# ATRescueBoard.net
KiCad netlist of a schematic drawn in EAGLE
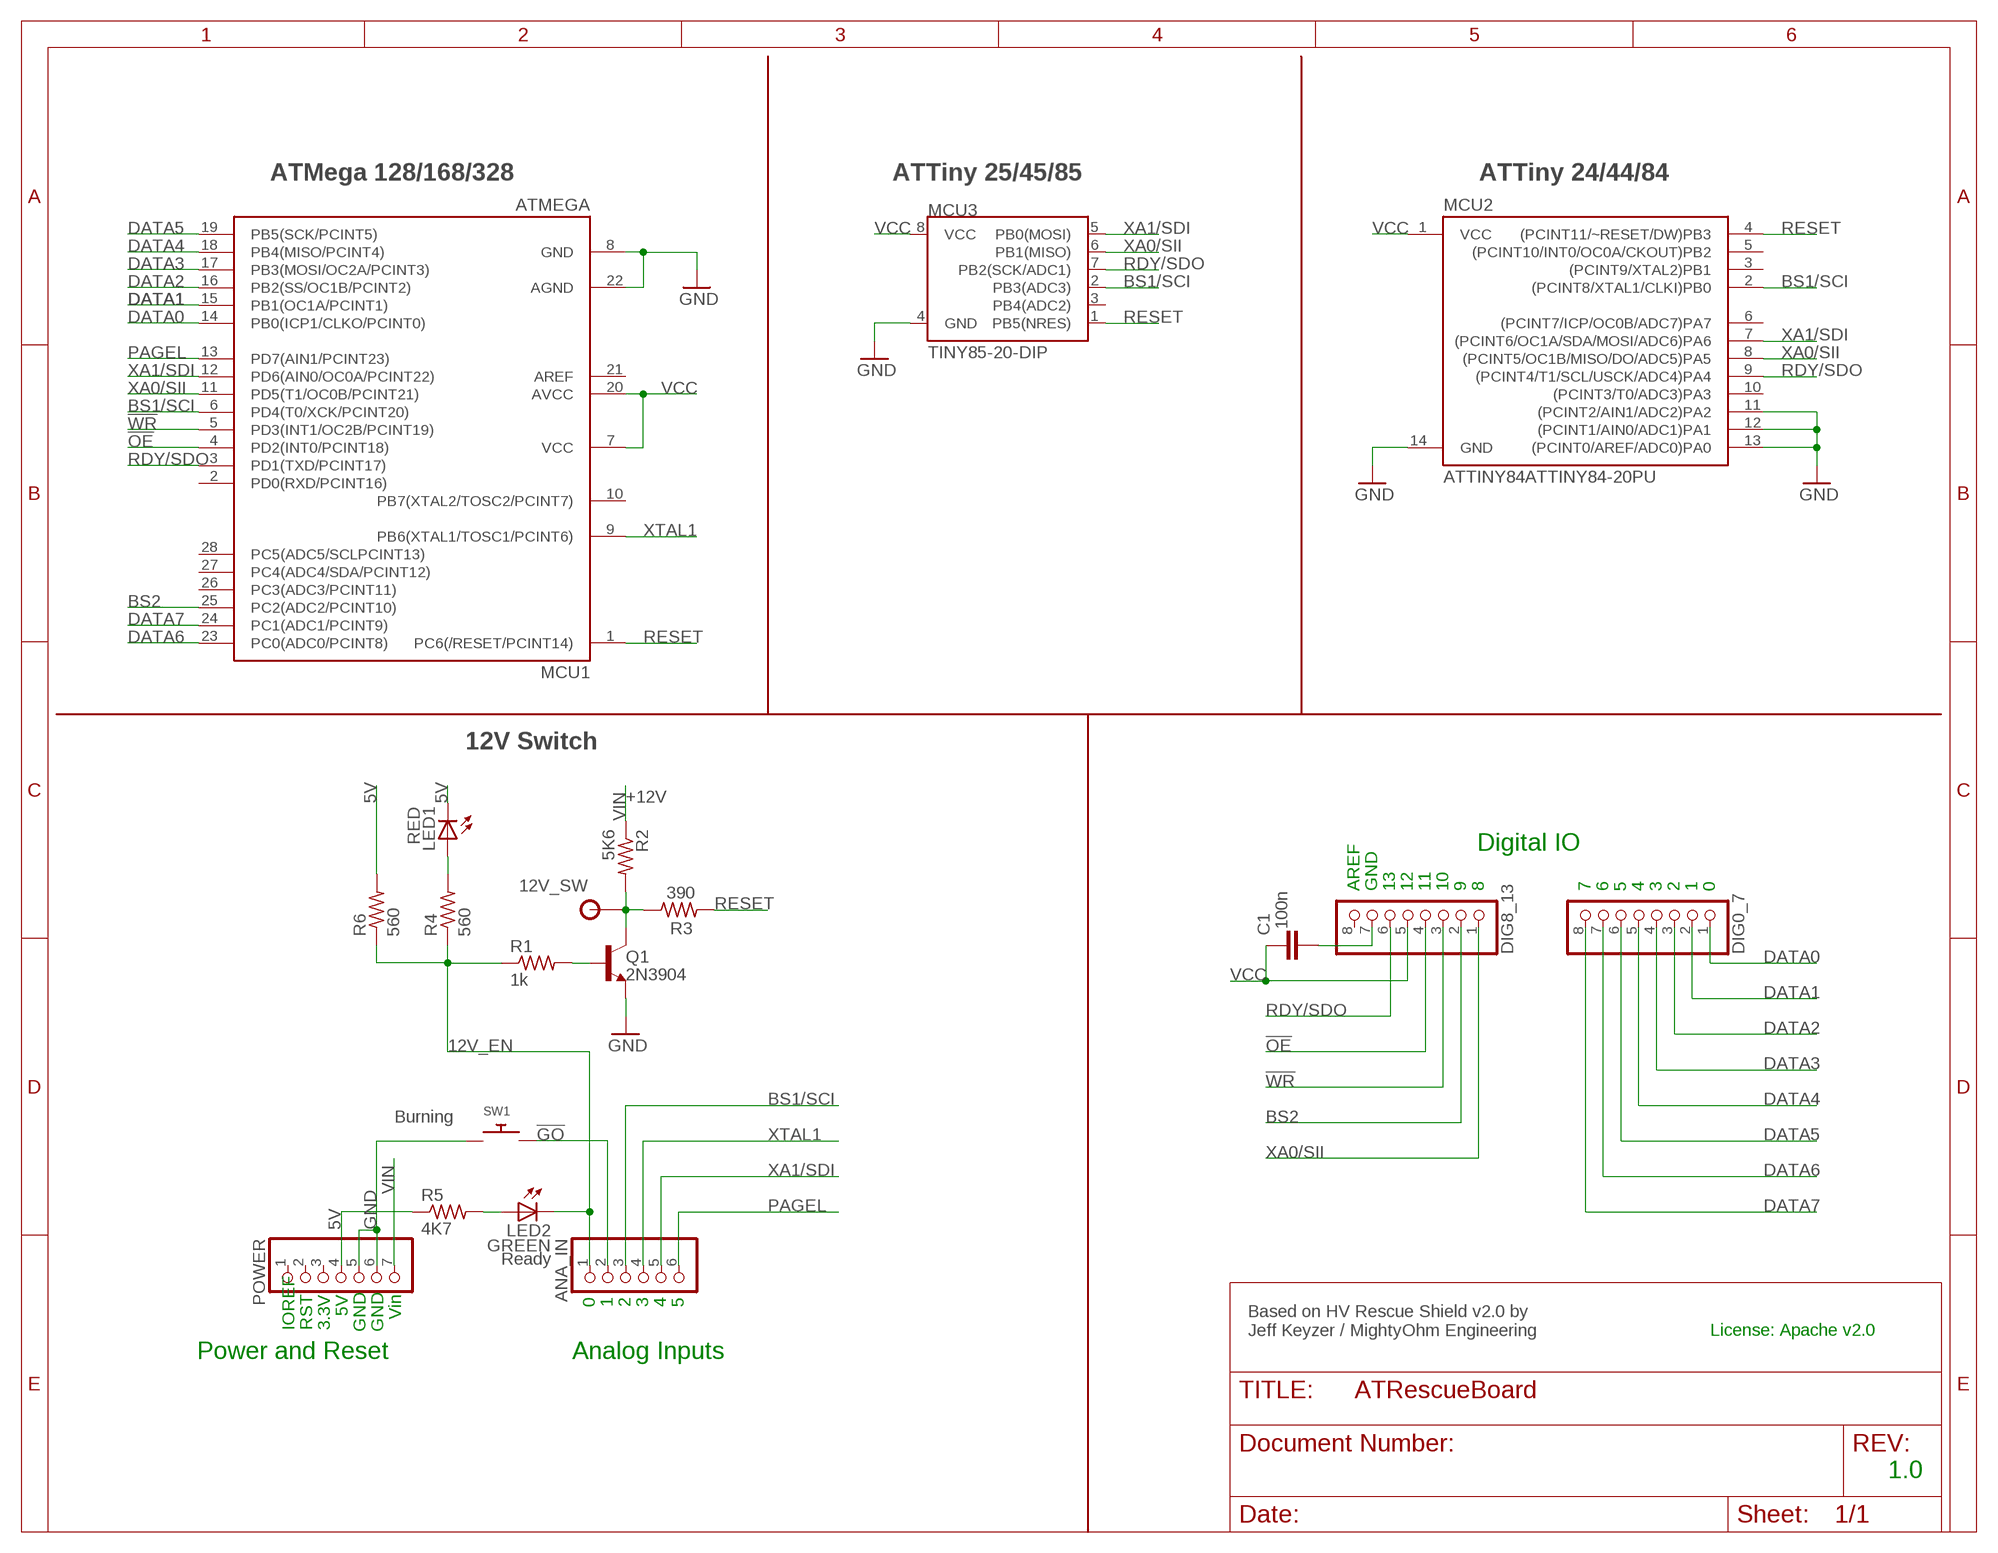
[diagram p0: schematic, sheet 1]

(export (version "E")
  (design (tool "Eeschema 10.0.6"))
  (components
    (comp (ref "ANA_IN")
      (value "PINHD-1X6")
      (footprint "eagle-import:1X06")
      (libsource (lib "eagle-import") (part "PINHD-1X6"))
    )
    (comp (ref "C1")
      (value "100n")
      (footprint "eagle-import:C050-024X044")
      (libsource (lib "eagle-import") (part "C-EU050-024X044"))
    )
    (comp (ref "DIG0_7")
      (value "PINHD-1X8")
      (footprint "eagle-import:1X08")
      (libsource (lib "eagle-import") (part "PINHD-1X8"))
    )
    (comp (ref "DIG8_13")
      (value "PINHD-1X8")
      (footprint "eagle-import:1X08")
      (libsource (lib "eagle-import") (part "PINHD-1X8"))
    )
    (comp (ref "LED1")
      (value "RED")
      (footprint "eagle-import:LED5MM")
      (libsource (lib "eagle-import") (part "LED5MM"))
    )
    (comp (ref "LED2")
      (value "GREEN")
      (footprint "eagle-import:LED5MM")
      (libsource (lib "eagle-import") (part "LED5MM"))
    )
    (comp (ref "MCU1")
      (value "ATMEGA")
      (footprint "eagle-import:DIL28-3")
      (libsource (lib "eagle-import") (part "MEGA48/88/168-PU"))
    )
    (comp (ref "MCU2")
      (value "ATTINY84ATTINY84-20PU")
      (footprint "eagle-import:DIL14")
      (libsource (lib "eagle-import") (part "ATTINY84ATTINY84-20PU"))
    )
    (comp (ref "MCU3")
      (value "TINY85-20-DIP")
      (footprint "eagle-import:DIP08")
      (libsource (lib "eagle-import") (part "ATTINY45TINY85-20-DIP"))
    )
    (comp (ref "POWER")
      (value "PINHD-1X7")
      (footprint "eagle-import:1X07")
      (libsource (lib "eagle-import") (part "PINHD-1X7"))
    )
    (comp (ref "Q1")
      (value "2N3904")
      (footprint "eagle-import:TO92-")
      (libsource (lib "eagle-import") (part "2N3904"))
    )
    (comp (ref "R1")
      (value "1k")
      (footprint "eagle-import:0204_7")
      (libsource (lib "eagle-import") (part "R-US_0204/7"))
    )
    (comp (ref "R2")
      (value "5K6")
      (footprint "eagle-import:0207_10")
      (libsource (lib "eagle-import") (part "R-US_0207/10"))
    )
    (comp (ref "R3")
      (value "390")
      (footprint "eagle-import:0309_12")
      (libsource (lib "eagle-import") (part "R-US_0309/12"))
    )
    (comp (ref "R4")
      (value "560")
      (footprint "eagle-import:0309_12")
      (libsource (lib "eagle-import") (part "R-US_0309/12"))
    )
    (comp (ref "R5")
      (value "4K7")
      (footprint "eagle-import:0204_7")
      (libsource (lib "eagle-import") (part "R-US_0204/7"))
    )
    (comp (ref "R6")
      (value "560")
      (footprint "eagle-import:0309_12")
      (libsource (lib "eagle-import") (part "R-US_0309/12"))
    )
    (comp (ref "SW1")
      (value "SWITCH_PUSHBUTTONEVQ-PE")
      (footprint "eagle-import:TACT_PANA-EVQ")
      (libsource (lib "eagle-import") (part "SWITCH_PUSHBUTTONEVQ-PE"))
    )
    (comp (ref "TP1")
      (value "12V_SW")
      (footprint "eagle-import:TP_PTH")
      (libsource (lib "eagle-import") (part "TPPTH"))
    )
  )
  (nets
    (net (code "1") (name "/5V") (class "Default")
      (node (ref "LED1") (pin "K") (pinfunction "C_K") (pintype "passive"))
      (node (ref "POWER") (pin "4") (pinfunction "4_4") (pintype "passive"))
      (node (ref "R5") (pin "1") (pinfunction "1_1") (pintype "passive"))
      (node (ref "R6") (pin "2") (pinfunction "2_2") (pintype "passive"))
    )
    (net (code "2") (name "/12V_EN") (class "Default")
      (node (ref "ANA_IN") (pin "1") (pinfunction "1_1") (pintype "passive"))
      (node (ref "LED2") (pin "K") (pinfunction "C_K") (pintype "passive"))
      (node (ref "R1") (pin "1") (pinfunction "1_1") (pintype "passive"))
      (node (ref "R4") (pin "1") (pinfunction "1_1") (pintype "passive"))
      (node (ref "R6") (pin "1") (pinfunction "1_1") (pintype "passive"))
    )
    (net (code "3") (name "/BS1{slash}SCI") (class "Default")
      (node (ref "ANA_IN") (pin "3") (pinfunction "3_3") (pintype "passive"))
      (node (ref "MCU1") (pin "6") (pinfunction "PD4(T0/XCK/PCINT20)_6") (pintype "bidirectional"))
      (node (ref "MCU2") (pin "2") (pinfunction "(PCINT8/XTAL1/CLKI)PB0_2") (pintype "bidirectional"))
      (node (ref "MCU3") (pin "2") (pinfunction "PB3(ADC3)_2") (pintype "bidirectional"))
    )
    (net (code "4") (name "/BS2") (class "Default")
      (node (ref "DIG8_13") (pin "2") (pinfunction "2_2") (pintype "passive"))
      (node (ref "MCU1") (pin "25") (pinfunction "PC2(ADC2/PCINT10)_25") (pintype "bidirectional"))
    )
    (net (code "5") (name "/DATA0") (class "Default")
      (node (ref "DIG0_7") (pin "1") (pinfunction "1_1") (pintype "passive"))
      (node (ref "MCU1") (pin "14") (pinfunction "PB0(ICP1/CLKO/PCINT0)_14") (pintype "bidirectional"))
    )
    (net (code "6") (name "/DATA1") (class "Default")
      (node (ref "DIG0_7") (pin "2") (pinfunction "2_2") (pintype "passive"))
      (node (ref "MCU1") (pin "15") (pinfunction "PB1(OC1A/PCINT1)_15") (pintype "bidirectional"))
    )
    (net (code "7") (name "/DATA2") (class "Default")
      (node (ref "DIG0_7") (pin "3") (pinfunction "3_3") (pintype "passive"))
      (node (ref "MCU1") (pin "16") (pinfunction "PB2(SS/OC1B/PCINT2)_16") (pintype "bidirectional"))
    )
    (net (code "8") (name "/DATA3") (class "Default")
      (node (ref "DIG0_7") (pin "4") (pinfunction "4_4") (pintype "passive"))
      (node (ref "MCU1") (pin "17") (pinfunction "PB3(MOSI/OC2A/PCINT3)_17") (pintype "bidirectional"))
    )
    (net (code "9") (name "/DATA4") (class "Default")
      (node (ref "DIG0_7") (pin "5") (pinfunction "5_5") (pintype "passive"))
      (node (ref "MCU1") (pin "18") (pinfunction "PB4(MISO/PCINT4)_18") (pintype "bidirectional"))
    )
    (net (code "10") (name "/DATA5") (class "Default")
      (node (ref "DIG0_7") (pin "6") (pinfunction "6_6") (pintype "passive"))
      (node (ref "MCU1") (pin "19") (pinfunction "PB5(SCK/PCINT5)_19") (pintype "bidirectional"))
    )
    (net (code "11") (name "/DATA6") (class "Default")
      (node (ref "DIG0_7") (pin "7") (pinfunction "7_7") (pintype "passive"))
      (node (ref "MCU1") (pin "23") (pinfunction "PC0(ADC0/PCINT8)_23") (pintype "bidirectional"))
    )
    (net (code "12") (name "/DATA7") (class "Default")
      (node (ref "DIG0_7") (pin "8") (pinfunction "8_8") (pintype "passive"))
      (node (ref "MCU1") (pin "24") (pinfunction "PC1(ADC1/PCINT9)_24") (pintype "bidirectional"))
    )
    (net (code "13") (name "/PAGEL") (class "Default")
      (node (ref "ANA_IN") (pin "6") (pinfunction "6_6") (pintype "passive"))
      (node (ref "MCU1") (pin "13") (pinfunction "PD7(AIN1/PCINT23)_13") (pintype "bidirectional"))
    )
    (net (code "14") (name "/RDY{slash}SDO") (class "Default")
      (node (ref "DIG8_13") (pin "6") (pinfunction "6_6") (pintype "passive"))
      (node (ref "MCU1") (pin "3") (pinfunction "PD1(TXD/PCINT17)_3") (pintype "bidirectional"))
      (node (ref "MCU2") (pin "9") (pinfunction "(PCINT4/T1/SCL/USCK/ADC4)PA4_9") (pintype "bidirectional"))
      (node (ref "MCU3") (pin "7") (pinfunction "PB2(SCK/ADC1)_7") (pintype "bidirectional"))
    )
    (net (code "15") (name "/RESET") (class "Default")
      (node (ref "MCU1") (pin "1") (pinfunction "PC6(/RESET/PCINT14)_1") (pintype "bidirectional"))
      (node (ref "MCU2") (pin "4") (pinfunction "(PCINT11/~{RESET/DW})PB3_4") (pintype "bidirectional"))
      (node (ref "MCU3") (pin "1") (pinfunction "PB5(NRES)_1") (pintype "bidirectional"))
      (node (ref "R3") (pin "2") (pinfunction "2_2") (pintype "passive"))
    )
    (net (code "16") (name "/VCC") (class "Default")
      (node (ref "C1") (pin "2") (pinfunction "2_2") (pintype "passive"))
      (node (ref "DIG8_13") (pin "5") (pinfunction "5_5") (pintype "passive"))
      (node (ref "MCU1") (pin "20") (pinfunction "AVCC_20") (pintype "passive"))
      (node (ref "MCU1") (pin "7") (pinfunction "VCC_7") (pintype "power_in"))
      (node (ref "MCU2") (pin "1") (pinfunction "VCC_1") (pintype "bidirectional"))
      (node (ref "MCU3") (pin "8") (pinfunction "VCC_8") (pintype "bidirectional"))
    )
    (net (code "17") (name "/VIN") (class "Default")
      (node (ref "POWER") (pin "7") (pinfunction "7_7") (pintype "passive"))
      (node (ref "R2") (pin "1") (pinfunction "1_1") (pintype "passive"))
    )
    (net (code "18") (name "/XA0{slash}SII") (class "Default")
      (node (ref "DIG8_13") (pin "1") (pinfunction "1_1") (pintype "passive"))
      (node (ref "MCU1") (pin "11") (pinfunction "PD5(T1/OC0B/PCINT21)_11") (pintype "bidirectional"))
      (node (ref "MCU2") (pin "8") (pinfunction "(PCINT5/OC1B/MISO/DO/ADC5)PA5_8") (pintype "bidirectional"))
      (node (ref "MCU3") (pin "6") (pinfunction "PB1(MISO)_6") (pintype "bidirectional"))
    )
    (net (code "19") (name "/XA1{slash}SDI") (class "Default")
      (node (ref "ANA_IN") (pin "5") (pinfunction "5_5") (pintype "passive"))
      (node (ref "MCU1") (pin "12") (pinfunction "PD6(AIN0/OC0A/PCINT22)_12") (pintype "bidirectional"))
      (node (ref "MCU2") (pin "7") (pinfunction "(PCINT6/OC1A/SDA/MOSI/ADC6)PA6_7") (pintype "bidirectional"))
      (node (ref "MCU3") (pin "5") (pinfunction "PB0(MOSI)_5") (pintype "bidirectional"))
    )
    (net (code "20") (name "/XTAL1") (class "Default")
      (node (ref "ANA_IN") (pin "4") (pinfunction "4_4") (pintype "passive"))
      (node (ref "MCU1") (pin "9") (pinfunction "PB6(XTAL1/TOSC1/PCINT6)_9") (pintype "bidirectional"))
    )
    (net (code "21") (name "/~{GO}") (class "Default")
      (node (ref "ANA_IN") (pin "2") (pinfunction "2_2") (pintype "passive"))
      (node (ref "SW1") (pin "P$2") (pinfunction "P$2_P$2") (pintype "passive"))
    )
    (net (code "22") (name "/~{OE}") (class "Default")
      (node (ref "DIG8_13") (pin "4") (pinfunction "4_4") (pintype "passive"))
      (node (ref "MCU1") (pin "4") (pinfunction "PD2(INT0/PCINT18)_4") (pintype "bidirectional"))
    )
    (net (code "23") (name "/~{WR}") (class "Default")
      (node (ref "DIG8_13") (pin "3") (pinfunction "3_3") (pintype "passive"))
      (node (ref "MCU1") (pin "5") (pinfunction "PD3(INT1/OC2B/PCINT19)_5") (pintype "bidirectional"))
    )
    (net (code "24") (name "GND") (class "Default")
      (node (ref "MCU1") (pin "22") (pinfunction "AGND_22") (pintype "power_in"))
      (node (ref "MCU1") (pin "8") (pinfunction "GND_8") (pintype "power_in"))
      (node (ref "MCU2") (pin "11") (pinfunction "(PCINT2/AIN1/ADC2)PA2_11") (pintype "bidirectional"))
      (node (ref "MCU2") (pin "12") (pinfunction "(PCINT1/AIN0/ADC1)PA1_12") (pintype "bidirectional"))
      (node (ref "MCU2") (pin "13") (pinfunction "(PCINT0/AREF/ADC0)PA0_13") (pintype "bidirectional"))
      (node (ref "MCU2") (pin "14") (pinfunction "GND_14") (pintype "bidirectional"))
      (node (ref "MCU3") (pin "4") (pinfunction "GND_4") (pintype "bidirectional"))
      (node (ref "POWER") (pin "5") (pinfunction "5_5") (pintype "passive"))
      (node (ref "POWER") (pin "6") (pinfunction "6_6") (pintype "passive"))
      (node (ref "Q1") (pin "3") (pinfunction "E_3") (pintype "passive"))
      (node (ref "SW1") (pin "P$1") (pinfunction "P$1_P$1") (pintype "passive"))
    )
    (net (code "25") (name "Net-(C1-Pad1)") (class "Default")
      (node (ref "C1") (pin "1") (pinfunction "1_1") (pintype "passive"))
      (node (ref "DIG8_13") (pin "7") (pinfunction "7_7") (pintype "passive"))
    )
    (net (code "26") (name "Net-(LED1-PadA)") (class "Default")
      (node (ref "LED1") (pin "A") (pinfunction "A_A") (pintype "passive"))
      (node (ref "R4") (pin "2") (pinfunction "2_2") (pintype "passive"))
    )
    (net (code "27") (name "Net-(LED2-PadA)") (class "Default")
      (node (ref "LED2") (pin "A") (pinfunction "A_A") (pintype "passive"))
      (node (ref "R5") (pin "2") (pinfunction "2_2") (pintype "passive"))
    )
    (net (code "28") (name "Net-(Q1-B)") (class "Default")
      (node (ref "Q1") (pin "2") (pinfunction "B_2") (pintype "passive"))
      (node (ref "R1") (pin "2") (pinfunction "2_2") (pintype "passive"))
    )
    (net (code "29") (name "Net-(Q1-C)") (class "Default")
      (node (ref "Q1") (pin "1") (pinfunction "C_1") (pintype "passive"))
      (node (ref "R2") (pin "2") (pinfunction "2_2") (pintype "passive"))
      (node (ref "R3") (pin "1") (pinfunction "1_1") (pintype "passive"))
      (node (ref "TP1") (pin "P$1") (pinfunction "TP_P$1") (pintype "bidirectional"))
    )
    (net (code "30") (name "unconnected-(DIG8_13-Pad8)") (class "Default")
      (node (ref "DIG8_13") (pin "8") (pinfunction "8_8") (pintype "passive"))
    )
    (net (code "31") (name "unconnected-(MCU1-AREF-Pad21)") (class "Default")
      (node (ref "MCU1") (pin "21") (pinfunction "AREF_21") (pintype "passive"))
    )
    (net (code "32") (name "unconnected-(MCU1-PB7(XTAL2{slash}TOSC2{slash}PCINT7)-Pad10)") (class "Default")
      (node (ref "MCU1") (pin "10") (pinfunction "PB7(XTAL2/TOSC2/PCINT7)_10") (pintype "bidirectional"))
    )
    (net (code "33") (name "unconnected-(MCU1-PC3(ADC3{slash}PCINT11)-Pad26)") (class "Default")
      (node (ref "MCU1") (pin "26") (pinfunction "PC3(ADC3/PCINT11)_26") (pintype "bidirectional"))
    )
    (net (code "34") (name "unconnected-(MCU1-PC4(ADC4{slash}SDA{slash}PCINT12)-Pad27)") (class "Default")
      (node (ref "MCU1") (pin "27") (pinfunction "PC4(ADC4/SDA/PCINT12)_27") (pintype "bidirectional"))
    )
    (net (code "35") (name "unconnected-(MCU1-PC5(ADC5{slash}SCLPCINT13)-Pad28)") (class "Default")
      (node (ref "MCU1") (pin "28") (pinfunction "PC5(ADC5/SCLPCINT13)_28") (pintype "bidirectional"))
    )
    (net (code "36") (name "unconnected-(MCU1-PD0(RXD{slash}PCINT16)-Pad2)") (class "Default")
      (node (ref "MCU1") (pin "2") (pinfunction "PD0(RXD/PCINT16)_2") (pintype "bidirectional"))
    )
    (net (code "37") (name "unconnected-(MCU2-(PCINT3{slash}T0{slash}ADC3)PA3-Pad10)") (class "Default")
      (node (ref "MCU2") (pin "10") (pinfunction "(PCINT3/T0/ADC3)PA3_10") (pintype "bidirectional"))
    )
    (net (code "38") (name "unconnected-(MCU2-(PCINT7{slash}ICP{slash}OC0B{slash}ADC7)PA7-Pad6)") (class "Default")
      (node (ref "MCU2") (pin "6") (pinfunction "(PCINT7/ICP/OC0B/ADC7)PA7_6") (pintype "bidirectional"))
    )
    (net (code "39") (name "unconnected-(MCU2-(PCINT9{slash}XTAL2)PB1-Pad3)") (class "Default")
      (node (ref "MCU2") (pin "3") (pinfunction "(PCINT9/XTAL2)PB1_3") (pintype "bidirectional"))
    )
    (net (code "40") (name "unconnected-(MCU2-(PCINT10{slash}INT0{slash}OC0A{slash}CKOUT)PB2-Pad5)") (class "Default")
      (node (ref "MCU2") (pin "5") (pinfunction "(PCINT10/INT0/OC0A/CKOUT)PB2_5") (pintype "bidirectional"))
    )
    (net (code "41") (name "unconnected-(MCU3-PB4(ADC2)-Pad3)") (class "Default")
      (node (ref "MCU3") (pin "3") (pinfunction "PB4(ADC2)_3") (pintype "bidirectional"))
    )
    (net (code "42") (name "unconnected-(POWER-Pad1)") (class "Default")
      (node (ref "POWER") (pin "1") (pinfunction "1_1") (pintype "passive"))
    )
    (net (code "43") (name "unconnected-(POWER-Pad2)") (class "Default")
      (node (ref "POWER") (pin "2") (pinfunction "2_2") (pintype "passive"))
    )
    (net (code "44") (name "unconnected-(POWER-Pad3)") (class "Default")
      (node (ref "POWER") (pin "3") (pinfunction "3_3") (pintype "passive"))
    )
  )
)
